# MySchematic.net
KiCad netlist of a schematic drawn in Altium Designer
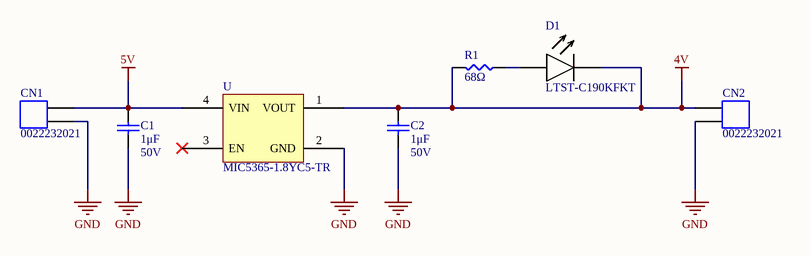
[diagram p0: MySchematic.SchDoc]

(export (version "E")
  (design (tool "Eeschema 10.0.6"))
  (components
    (comp (ref "C1")
      (value "1μF")
      (footprint "CAP0805")
      (description "CAP CER 1PF 50V C0G/NP0 0402")
      (fields (field (name "VOLTAGE RATING") "50V") (field (name "Comment") "GCM21BR71E105KA56L_1"))
      (libsource (lib "Bootcamp_Schematic_Library") (part "GCM21BR71E105KA56L_1"))
    )
    (comp (ref "C2")
      (value "1μF")
      (footprint "CAP0805")
      (description "CAP CER 1PF 50V C0G/NP0 0402")
      (fields (field (name "VOLTAGE RATING") "50V") (field (name "Comment") "GCM21BR71E105KA56L_1"))
      (libsource (lib "Bootcamp_Schematic_Library") (part "GCM21BR71E105KA56L_1"))
    )
    (comp (ref "CN1")
      (value "0022232021")
      (footprint "900-0022232021-ND")
      (description "CONN HEADER VERT 2POS 2.54MM")
      (libsource (lib "Bootcamp_Schematic_Library") (part "0022232021"))
    )
    (comp (ref "CN2")
      (value "0022232021")
      (footprint "900-0022232021-ND")
      (description "CONN HEADER VERT 2POS 2.54MM")
      (libsource (lib "") (part "0022232021_1"))
    )
    (comp (ref "D1")
      (value "LTST-C190KFKT")
      (footprint "0603 (1608 Metric)")
      (description "ED ORANGE CLEAR CHIP SMD")
      (libsource (lib "Bootcamp_Schematic_Library") (part "LTST-C190KFKT"))
    )
    (comp (ref "R1")
      (value "68Ω")
      (footprint "RES0603")
      (description "RES 68 OHM 5% 1/10W 0603")
      (fields (field (name "Comment") "RC0603JR-0768RL"))
      (libsource (lib "Bootcamp_Schematic_Library") (part "RC0603JR-0768RL"))
    )
    (comp (ref "U")
      (value "MIC5365-1.8YC5-TR")
      (footprint "576-3181-6-ND")
      (description "IC REG LINEAR 1.8V 150MA SC-70-5")
      (libsource (lib "Bootcamp_Schematic_Library") (part "MIC5365-1.8YC5-TR"))
    )
  )
  (nets
    (net (code "1") (name "4V") (class "Default")
      (node (ref "C2") (pin "2") (pinfunction "2_2") (pintype "passive"))
      (node (ref "CN2") (pin "2") (pinfunction "2_2") (pintype "passive"))
      (node (ref "D1") (pin "2") (pintype "passive"))
      (node (ref "R1") (pin "1") (pinfunction "1_1") (pintype "passive"))
      (node (ref "U") (pin "1") (pinfunction "VOUT_1") (pintype "passive"))
    )
    (net (code "2") (name "5V") (class "Default")
      (node (ref "C1") (pin "2") (pinfunction "2_2") (pintype "passive"))
      (node (ref "CN1") (pin "1") (pinfunction "1_1") (pintype "passive"))
      (node (ref "U") (pin "4") (pinfunction "VIN_4") (pintype "passive"))
    )
    (net (code "3") (name "GND") (class "Default")
      (node (ref "C1") (pin "1") (pinfunction "1_1") (pintype "passive"))
      (node (ref "C2") (pin "1") (pinfunction "1_1") (pintype "passive"))
      (node (ref "CN1") (pin "2") (pinfunction "2_2") (pintype "passive"))
      (node (ref "CN2") (pin "1") (pinfunction "1_1") (pintype "passive"))
      (node (ref "U") (pin "2") (pinfunction "GND_2") (pintype "passive"))
    )
    (net (code "4") (name "Net-(D1-Pad1)") (class "Default")
      (node (ref "D1") (pin "1") (pintype "passive"))
      (node (ref "R1") (pin "2") (pinfunction "2_2") (pintype "passive"))
    )
    (net (code "5") (name "unconnected-(U-EN-Pad3)") (class "Default")
      (node (ref "U") (pin "3") (pinfunction "EN_3") (pintype "passive+no_connect"))
    )
  )
)
